# LM2735b.net
KiCad netlist of a schematic drawn in EAGLE
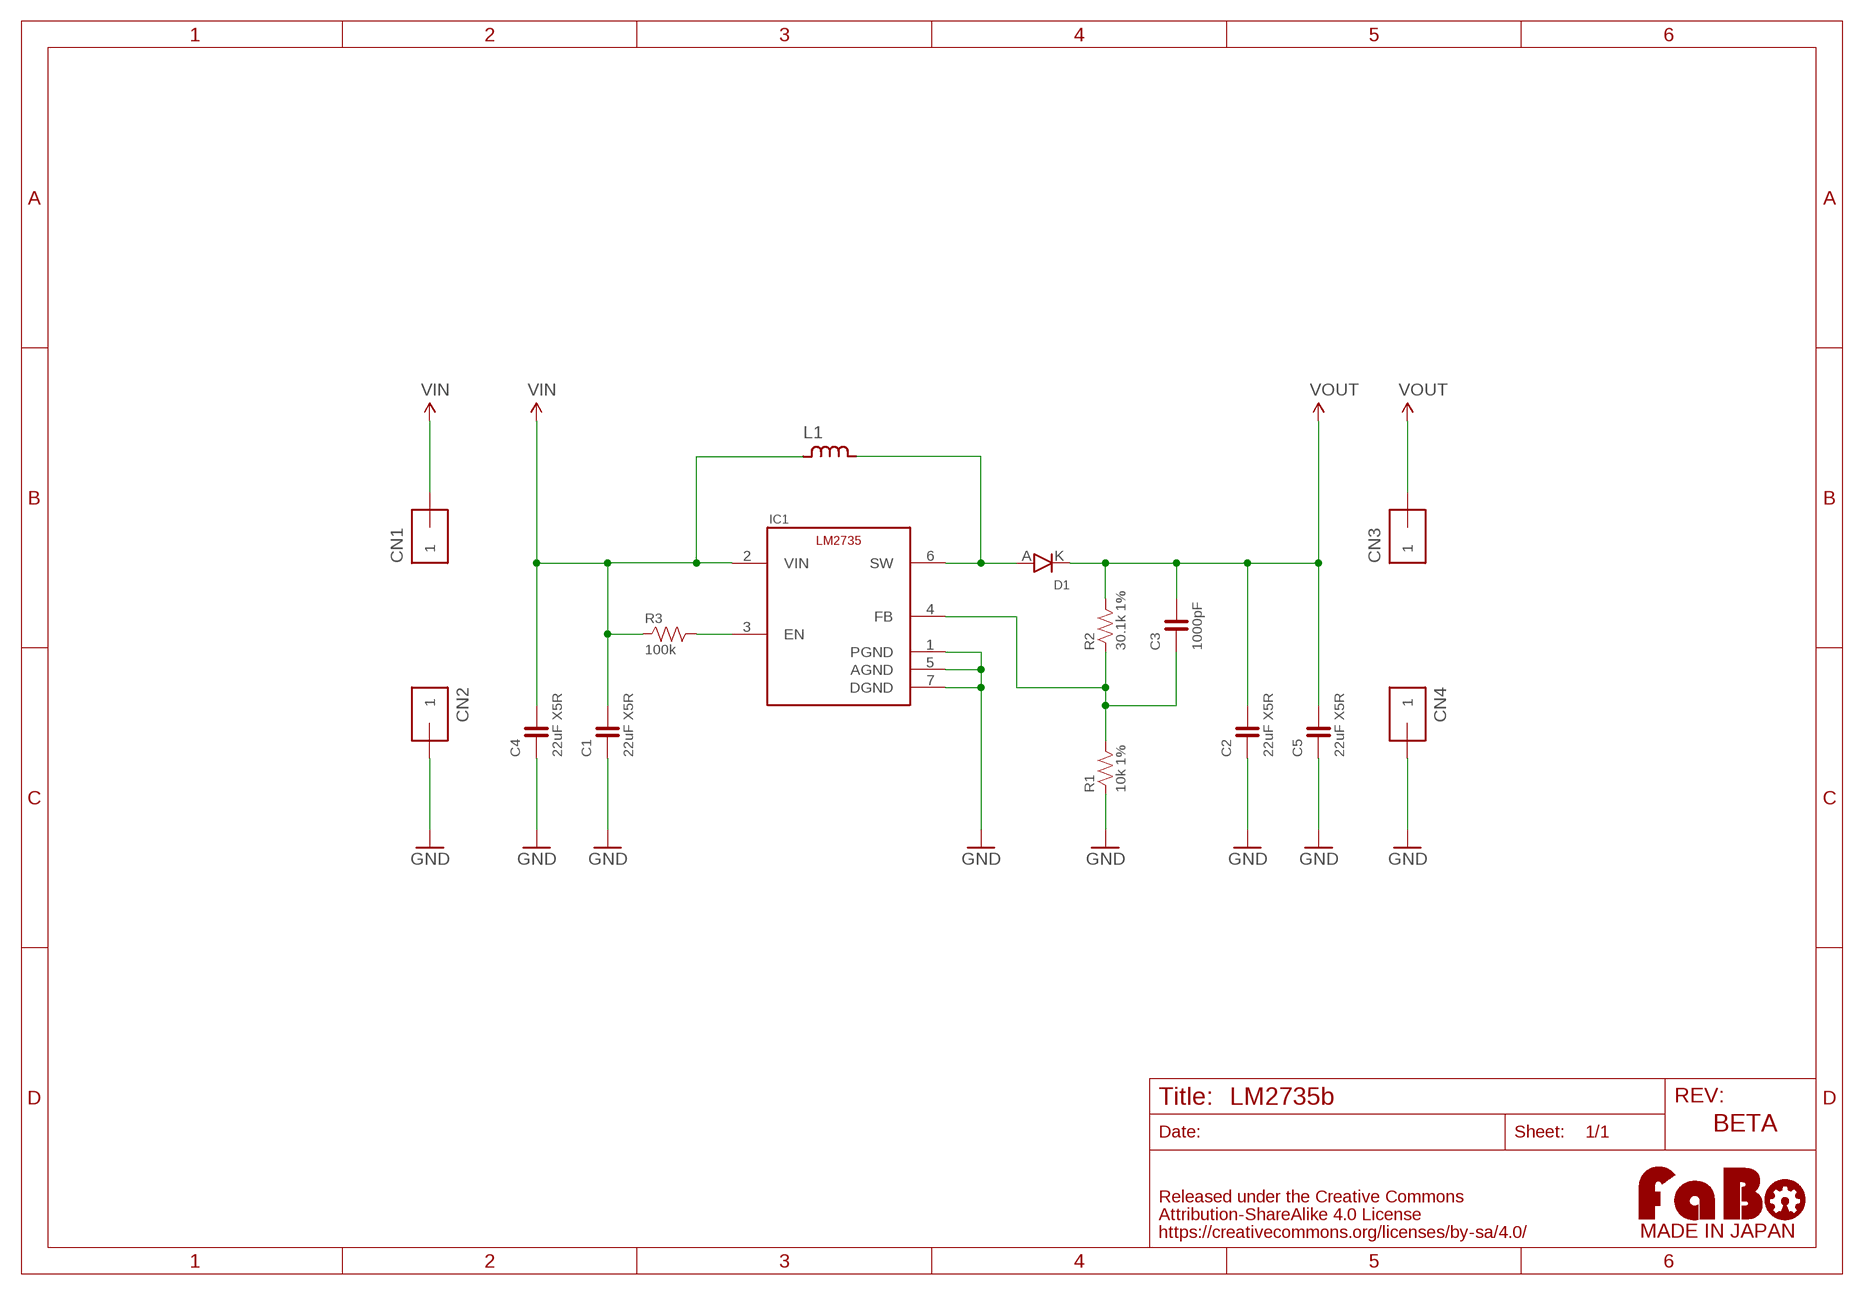
[diagram p0: schematic, sheet 1]

(export (version "E")
  (design (tool "Eeschema 10.0.6"))
  (components
    (comp (ref "C1")
      (value "22uF X5R")
      (footprint "eagle-import:0603-NARROW")
      (libsource (lib "eagle-import") (part "CAPACITOR-0603_NARROW"))
    )
    (comp (ref "C2")
      (value "22uF X5R")
      (footprint "eagle-import:0603-NARROW")
      (libsource (lib "eagle-import") (part "CAPACITOR-0603_NARROW"))
    )
    (comp (ref "C3")
      (value "1000pF")
      (footprint "eagle-import:0603-NARROW")
      (libsource (lib "eagle-import") (part "CAPACITOR-0603_NARROW"))
    )
    (comp (ref "C4")
      (value "22uF X5R")
      (footprint "eagle-import:0603-NARROW")
      (libsource (lib "eagle-import") (part "CAPACITOR-0603_NARROW"))
    )
    (comp (ref "C5")
      (value "22uF X5R")
      (footprint "eagle-import:0603-NARROW")
      (libsource (lib "eagle-import") (part "CAPACITOR-0603_NARROW"))
    )
    (comp (ref "CN1")
      (value "PIN_HEADER_1X1-SMALL")
      (footprint "eagle-import:PIN_1X1_SMALL")
      (libsource (lib "eagle-import") (part "PIN_HEADER_1X1-SMALL"))
    )
    (comp (ref "CN2")
      (value "PIN_HEADER_1X1-SMALL")
      (footprint "eagle-import:PIN_1X1_SMALL")
      (libsource (lib "eagle-import") (part "PIN_HEADER_1X1-SMALL"))
    )
    (comp (ref "CN3")
      (value "PIN_HEADER_1X1-SMALL")
      (footprint "eagle-import:PIN_1X1_SMALL")
      (libsource (lib "eagle-import") (part "PIN_HEADER_1X1-SMALL"))
    )
    (comp (ref "CN4")
      (value "PIN_HEADER_1X1-SMALL")
      (footprint "eagle-import:PIN_1X1_SMALL")
      (libsource (lib "eagle-import") (part "PIN_HEADER_1X1-SMALL"))
    )
    (comp (ref "D1")
      (value "DIODE-STPS120MF")
      (footprint "eagle-import:ST-MITE-FLAT")
      (libsource (lib "eagle-import") (part "DIODE-STPS120MF"))
    )
    (comp (ref "IC1")
      (value "LM2735YQSDX")
      (footprint "eagle-import:WSON-6")
      (libsource (lib "eagle-import") (part "LM2735YQSDX"))
    )
    (comp (ref "L1")
      (value "INDUCTOR-NR6028")
      (footprint "eagle-import:NR6028")
      (libsource (lib "eagle-import") (part "INDUCTOR-NR6028"))
    )
    (comp (ref "R1")
      (value "10k 1%")
      (footprint "eagle-import:0603-NARROW")
      (libsource (lib "eagle-import") (part "RESISTOR-0603-NARROW"))
    )
    (comp (ref "R2")
      (value "30.1k 1%")
      (footprint "eagle-import:0603-NARROW")
      (libsource (lib "eagle-import") (part "RESISTOR-0603-NARROW"))
    )
    (comp (ref "R3")
      (value "100k")
      (footprint "eagle-import:0603-NARROW")
      (libsource (lib "eagle-import") (part "RESISTOR-0603-NARROW"))
    )
    (comp (ref "U$2")
      (value "LOGO_FABO-M_BOTTOM")
      (footprint "eagle-import:LOGO_FABO_MS_BOTTOM")
      (libsource (lib "eagle-import") (part "LOGO_FABO-M_BOTTOM"))
    )
  )
  (nets
    (net (code "1") (name "GND") (class "Default")
      (node (ref "C1") (pin "1") (pinfunction "1_1") (pintype "passive"))
      (node (ref "C2") (pin "1") (pinfunction "1_1") (pintype "passive"))
      (node (ref "C4") (pin "1") (pinfunction "1_1") (pintype "passive"))
      (node (ref "C5") (pin "1") (pinfunction "1_1") (pintype "passive"))
      (node (ref "CN2") (pin "1") (pinfunction "1_1") (pintype "bidirectional"))
      (node (ref "CN4") (pin "1") (pinfunction "1_1") (pintype "bidirectional"))
      (node (ref "IC1") (pin "1") (pinfunction "PGND_1") (pintype "bidirectional"))
      (node (ref "IC1") (pin "5") (pinfunction "AGND_5") (pintype "bidirectional"))
      (node (ref "IC1") (pin "7") (pinfunction "DGND_7") (pintype "bidirectional"))
      (node (ref "R1") (pin "1") (pinfunction "1_1") (pintype "bidirectional"))
    )
    (net (code "2") (name "Net-(IC1-EN)") (class "Default")
      (node (ref "IC1") (pin "3") (pinfunction "EN_3") (pintype "bidirectional"))
      (node (ref "R3") (pin "2") (pinfunction "2_2") (pintype "bidirectional"))
    )
    (net (code "3") (name "Net-(IC1-FB)") (class "Default")
      (node (ref "C3") (pin "1") (pinfunction "1_1") (pintype "passive"))
      (node (ref "IC1") (pin "4") (pinfunction "FB_4") (pintype "bidirectional"))
      (node (ref "R1") (pin "2") (pinfunction "2_2") (pintype "bidirectional"))
      (node (ref "R2") (pin "1") (pinfunction "1_1") (pintype "bidirectional"))
    )
    (net (code "4") (name "Net-(IC1-SW)") (class "Default")
      (node (ref "D1") (pin "A") (pinfunction "A_A") (pintype "bidirectional"))
      (node (ref "IC1") (pin "6") (pinfunction "SW_6") (pintype "bidirectional"))
      (node (ref "L1") (pin "2") (pinfunction "2_2") (pintype "bidirectional"))
    )
    (net (code "5") (name "VIN") (class "Default")
      (node (ref "C1") (pin "2") (pinfunction "2_2") (pintype "passive"))
      (node (ref "C4") (pin "2") (pinfunction "2_2") (pintype "passive"))
      (node (ref "CN1") (pin "1") (pinfunction "1_1") (pintype "bidirectional"))
      (node (ref "IC1") (pin "2") (pinfunction "VIN_2") (pintype "bidirectional"))
      (node (ref "L1") (pin "1") (pinfunction "1_1") (pintype "bidirectional"))
      (node (ref "R3") (pin "1") (pinfunction "1_1") (pintype "bidirectional"))
    )
    (net (code "6") (name "VOUT") (class "Default")
      (node (ref "C2") (pin "2") (pinfunction "2_2") (pintype "passive"))
      (node (ref "C3") (pin "2") (pinfunction "2_2") (pintype "passive"))
      (node (ref "C5") (pin "2") (pinfunction "2_2") (pintype "passive"))
      (node (ref "CN3") (pin "1") (pinfunction "1_1") (pintype "bidirectional"))
      (node (ref "D1") (pin "K") (pinfunction "K_K") (pintype "bidirectional"))
      (node (ref "R2") (pin "2") (pinfunction "2_2") (pintype "bidirectional"))
    )
  )
)
